# max6_breakout_lcv2.net
KiCad netlist of a schematic drawn in EAGLE
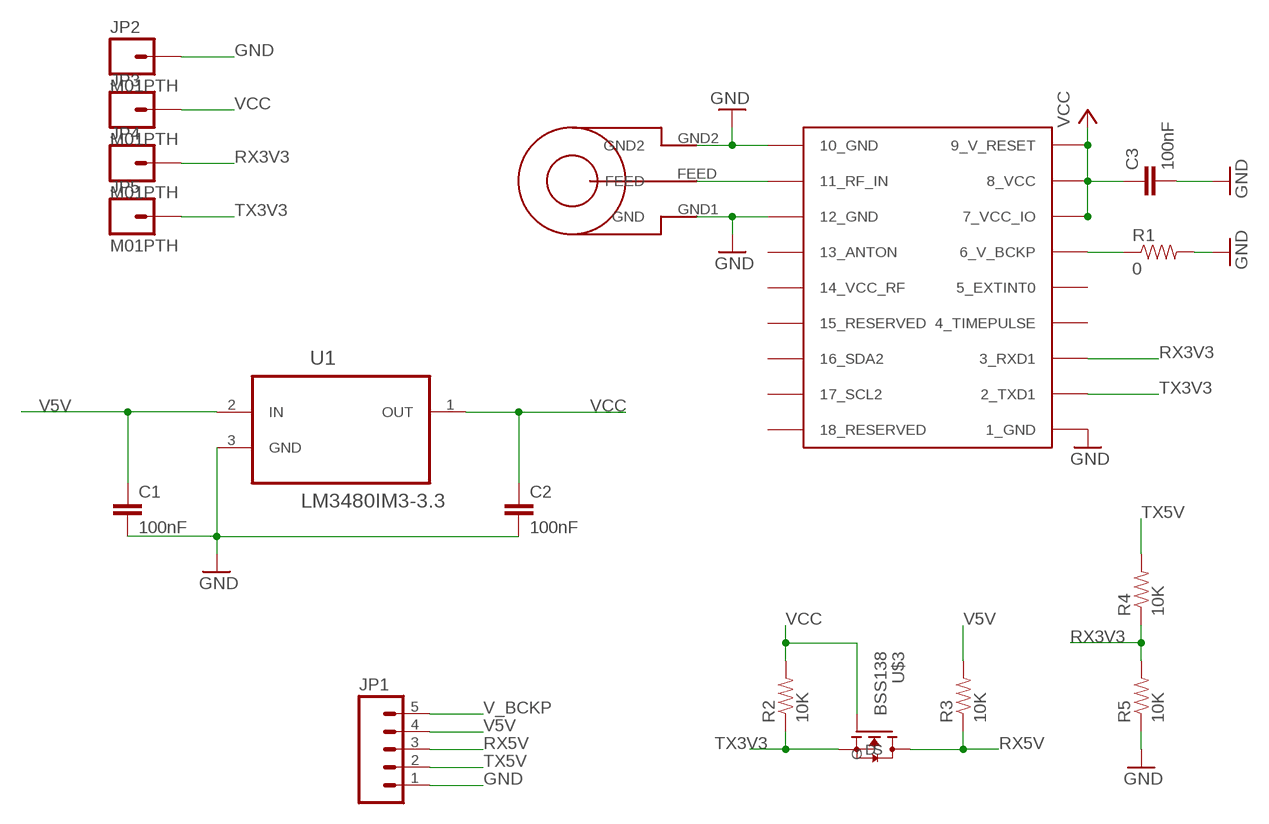
[diagram p0: schematic, sheet 1]

(export (version "E")
  (design (tool "Eeschema 10.0.6"))
  (components
    (comp (ref "C1")
      (value "100nF")
      (footprint "eagle-import:0603-CAP")
      (libsource (lib "eagle-import") (part "CAP0603-CAP"))
    )
    (comp (ref "C2")
      (value "100nF")
      (footprint "eagle-import:0603-CAP")
      (libsource (lib "eagle-import") (part "CAP0603-CAP"))
    )
    (comp (ref "C3")
      (value "100nF")
      (footprint "eagle-import:0603-CAP")
      (libsource (lib "eagle-import") (part "CAP0603-CAP"))
    )
    (comp (ref "JP1")
      (value "M05PTH")
      (footprint "eagle-import:1X05")
      (libsource (lib "eagle-import") (part "M05PTH"))
    )
    (comp (ref "JP2")
      (value "M01PTH")
      (footprint "eagle-import:1X01")
      (libsource (lib "eagle-import") (part "M01PTH"))
    )
    (comp (ref "JP3")
      (value "M01PTH")
      (footprint "eagle-import:1X01")
      (libsource (lib "eagle-import") (part "M01PTH"))
    )
    (comp (ref "JP4")
      (value "M01PTH")
      (footprint "eagle-import:1X01")
      (libsource (lib "eagle-import") (part "M01PTH"))
    )
    (comp (ref "JP5")
      (value "M01PTH")
      (footprint "eagle-import:1X01")
      (libsource (lib "eagle-import") (part "M01PTH"))
    )
    (comp (ref "R1")
      (value "0")
      (footprint "eagle-import:0603-RES")
      (libsource (lib "eagle-import") (part "RESISTOR0603-RES"))
    )
    (comp (ref "R2")
      (value "10K")
      (footprint "eagle-import:0603-RES")
      (libsource (lib "eagle-import") (part "RESISTOR0603-RES"))
    )
    (comp (ref "R3")
      (value "10K")
      (footprint "eagle-import:0603-RES")
      (libsource (lib "eagle-import") (part "RESISTOR0603-RES"))
    )
    (comp (ref "R4")
      (value "10K")
      (footprint "eagle-import:0603-RES")
      (libsource (lib "eagle-import") (part "RESISTOR0603-RES"))
    )
    (comp (ref "R5")
      (value "10K")
      (footprint "eagle-import:0603-RES")
      (libsource (lib "eagle-import") (part "RESISTOR0603-RES"))
    )
    (comp (ref "U$1")
      (value "UBLOX_MAX-6")
      (footprint "eagle-import:UBLOX_MAX-6")
      (libsource (lib "eagle-import") (part "UBLOX_MAX-6"))
    )
    (comp (ref "U$2")
      (value "SARANTEL-SR1202")
      (footprint "eagle-import:SARANTEL-SR1202")
      (libsource (lib "eagle-import") (part "SARANTEL-SR1202"))
    )
    (comp (ref "U$3")
      (value "BSS138")
      (footprint "eagle-import:BSS138")
      (libsource (lib "eagle-import") (part "BSS138"))
    )
    (comp (ref "U1")
      (value "LM3480IM3-3.3")
      (footprint "eagle-import:SOT95P251X112-3N")
      (libsource (lib "eagle-import") (part "LM3480IM3-3.3"))
    )
  )
  (nets
    (net (code "1") (name "/RX3V3") (class "Default")
      (node (ref "JP4") (pin "1") (pinfunction "1_1") (pintype "passive"))
      (node (ref "R4") (pin "1") (pinfunction "1_1") (pintype "passive"))
      (node (ref "R5") (pin "2") (pinfunction "2_2") (pintype "passive"))
      (node (ref "U$1") (pin "3_RXD1") (pinfunction "3_RXD1_3_RXD1") (pintype "bidirectional"))
    )
    (net (code "2") (name "/RX5V") (class "Default")
      (node (ref "JP1") (pin "3") (pinfunction "3_3") (pintype "passive"))
      (node (ref "R3") (pin "1") (pinfunction "1_1") (pintype "passive"))
      (node (ref "U$3") (pin "D") (pinfunction "D_D") (pintype "passive"))
    )
    (net (code "3") (name "/TX3V3") (class "Default")
      (node (ref "JP5") (pin "1") (pinfunction "1_1") (pintype "passive"))
      (node (ref "R2") (pin "1") (pinfunction "1_1") (pintype "passive"))
      (node (ref "U$1") (pin "2_TXD1") (pinfunction "2_TXD1_2_TXD1") (pintype "bidirectional"))
      (node (ref "U$3") (pin "S") (pinfunction "S_S") (pintype "passive"))
    )
    (net (code "4") (name "/TX5V") (class "Default")
      (node (ref "JP1") (pin "2") (pinfunction "2_2") (pintype "passive"))
      (node (ref "R4") (pin "2") (pinfunction "2_2") (pintype "passive"))
    )
    (net (code "5") (name "/V5V") (class "Default")
      (node (ref "C1") (pin "1") (pinfunction "1_1") (pintype "passive"))
      (node (ref "JP1") (pin "4") (pinfunction "4_4") (pintype "passive"))
      (node (ref "R3") (pin "2") (pinfunction "2_2") (pintype "passive"))
      (node (ref "U1") (pin "2") (pinfunction "IN_2") (pintype "power_in"))
    )
    (net (code "6") (name "/V_BCKP") (class "Default")
      (node (ref "JP1") (pin "5") (pinfunction "5_5") (pintype "passive"))
      (node (ref "R1") (pin "1") (pinfunction "1_1") (pintype "passive"))
      (node (ref "U$1") (pin "6_V_BCKP") (pinfunction "6_V_BCKP_6_V_BCKP") (pintype "bidirectional"))
    )
    (net (code "7") (name "GND") (class "Default")
      (node (ref "C1") (pin "2") (pinfunction "2_2") (pintype "passive"))
      (node (ref "C2") (pin "2") (pinfunction "2_2") (pintype "passive"))
      (node (ref "C3") (pin "2") (pinfunction "2_2") (pintype "passive"))
      (node (ref "JP1") (pin "1") (pinfunction "1_1") (pintype "passive"))
      (node (ref "JP2") (pin "1") (pinfunction "1_1") (pintype "passive"))
      (node (ref "R1") (pin "2") (pinfunction "2_2") (pintype "passive"))
      (node (ref "R5") (pin "1") (pinfunction "1_1") (pintype "passive"))
      (node (ref "U$1") (pin "10_GND") (pinfunction "10_GND_10_GND") (pintype "bidirectional"))
      (node (ref "U$1") (pin "12_GND") (pinfunction "12_GND_12_GND") (pintype "bidirectional"))
      (node (ref "U$1") (pin "1_GND") (pinfunction "1_GND_1_GND") (pintype "bidirectional"))
      (node (ref "U$2") (pin "GND1") (pinfunction "GND_GND1") (pintype "bidirectional"))
      (node (ref "U$2") (pin "GND2") (pinfunction "GND2_GND2") (pintype "bidirectional"))
      (node (ref "U1") (pin "3") (pinfunction "GND_3") (pintype "passive"))
    )
    (net (code "8") (name "Net-(U$1-Pad11_RF_IN)") (class "Default")
      (node (ref "U$1") (pin "11_RF_IN") (pinfunction "11_RF_IN_11_RF_IN") (pintype "bidirectional"))
      (node (ref "U$2") (pin "FEED") (pinfunction "FEED_FEED") (pintype "bidirectional"))
    )
    (net (code "9") (name "VCC") (class "Default")
      (node (ref "C2") (pin "1") (pinfunction "1_1") (pintype "passive"))
      (node (ref "C3") (pin "1") (pinfunction "1_1") (pintype "passive"))
      (node (ref "JP3") (pin "1") (pinfunction "1_1") (pintype "passive"))
      (node (ref "R2") (pin "2") (pinfunction "2_2") (pintype "passive"))
      (node (ref "U$1") (pin "7_VCC_IO") (pinfunction "7_VCC_IO_7_VCC_IO") (pintype "bidirectional"))
      (node (ref "U$1") (pin "8_VCC") (pinfunction "8_VCC_8_VCC") (pintype "bidirectional"))
      (node (ref "U$1") (pin "9_V_RESET") (pinfunction "9_V_RESET_9_V_RESET") (pintype "bidirectional"))
      (node (ref "U$3") (pin "G") (pinfunction "G_G") (pintype "passive"))
      (node (ref "U1") (pin "1") (pinfunction "OUT_1") (pintype "output"))
    )
    (net (code "10") (name "unconnected-(U$1-Pad4_TIMEPULSE)") (class "Default")
      (node (ref "U$1") (pin "4_TIMEPULSE") (pinfunction "4_TIMEPULSE_4_TIMEPULSE") (pintype "bidirectional"))
    )
    (net (code "11") (name "unconnected-(U$1-Pad5_EXTINT0)") (class "Default")
      (node (ref "U$1") (pin "5_EXTINT0") (pinfunction "5_EXTINT0_5_EXTINT0") (pintype "bidirectional"))
    )
    (net (code "12") (name "unconnected-(U$1-Pad13_ANTON)") (class "Default")
      (node (ref "U$1") (pin "13_ANTON") (pinfunction "13_ANTON_13_ANTON") (pintype "bidirectional"))
    )
    (net (code "13") (name "unconnected-(U$1-Pad14_VCC_RF)") (class "Default")
      (node (ref "U$1") (pin "14_VCC_RF") (pinfunction "14_VCC_RF_14_VCC_RF") (pintype "bidirectional"))
    )
    (net (code "14") (name "unconnected-(U$1-Pad15_RESERVED)") (class "Default")
      (node (ref "U$1") (pin "15_RESERVED") (pinfunction "15_RESERVED_15_RESERVED") (pintype "bidirectional"))
    )
    (net (code "15") (name "unconnected-(U$1-Pad16_SDA2)") (class "Default")
      (node (ref "U$1") (pin "16_SDA2") (pinfunction "16_SDA2_16_SDA2") (pintype "bidirectional"))
    )
    (net (code "16") (name "unconnected-(U$1-Pad17_SCL2)") (class "Default")
      (node (ref "U$1") (pin "17_SCL2") (pinfunction "17_SCL2_17_SCL2") (pintype "bidirectional"))
    )
    (net (code "17") (name "unconnected-(U$1-Pad18_RESERVED)") (class "Default")
      (node (ref "U$1") (pin "18_RESERVED") (pinfunction "18_RESERVED_18_RESERVED") (pintype "bidirectional"))
    )
  )
)
